# swimate_display.net
KiCad netlist of a schematic drawn in EAGLE
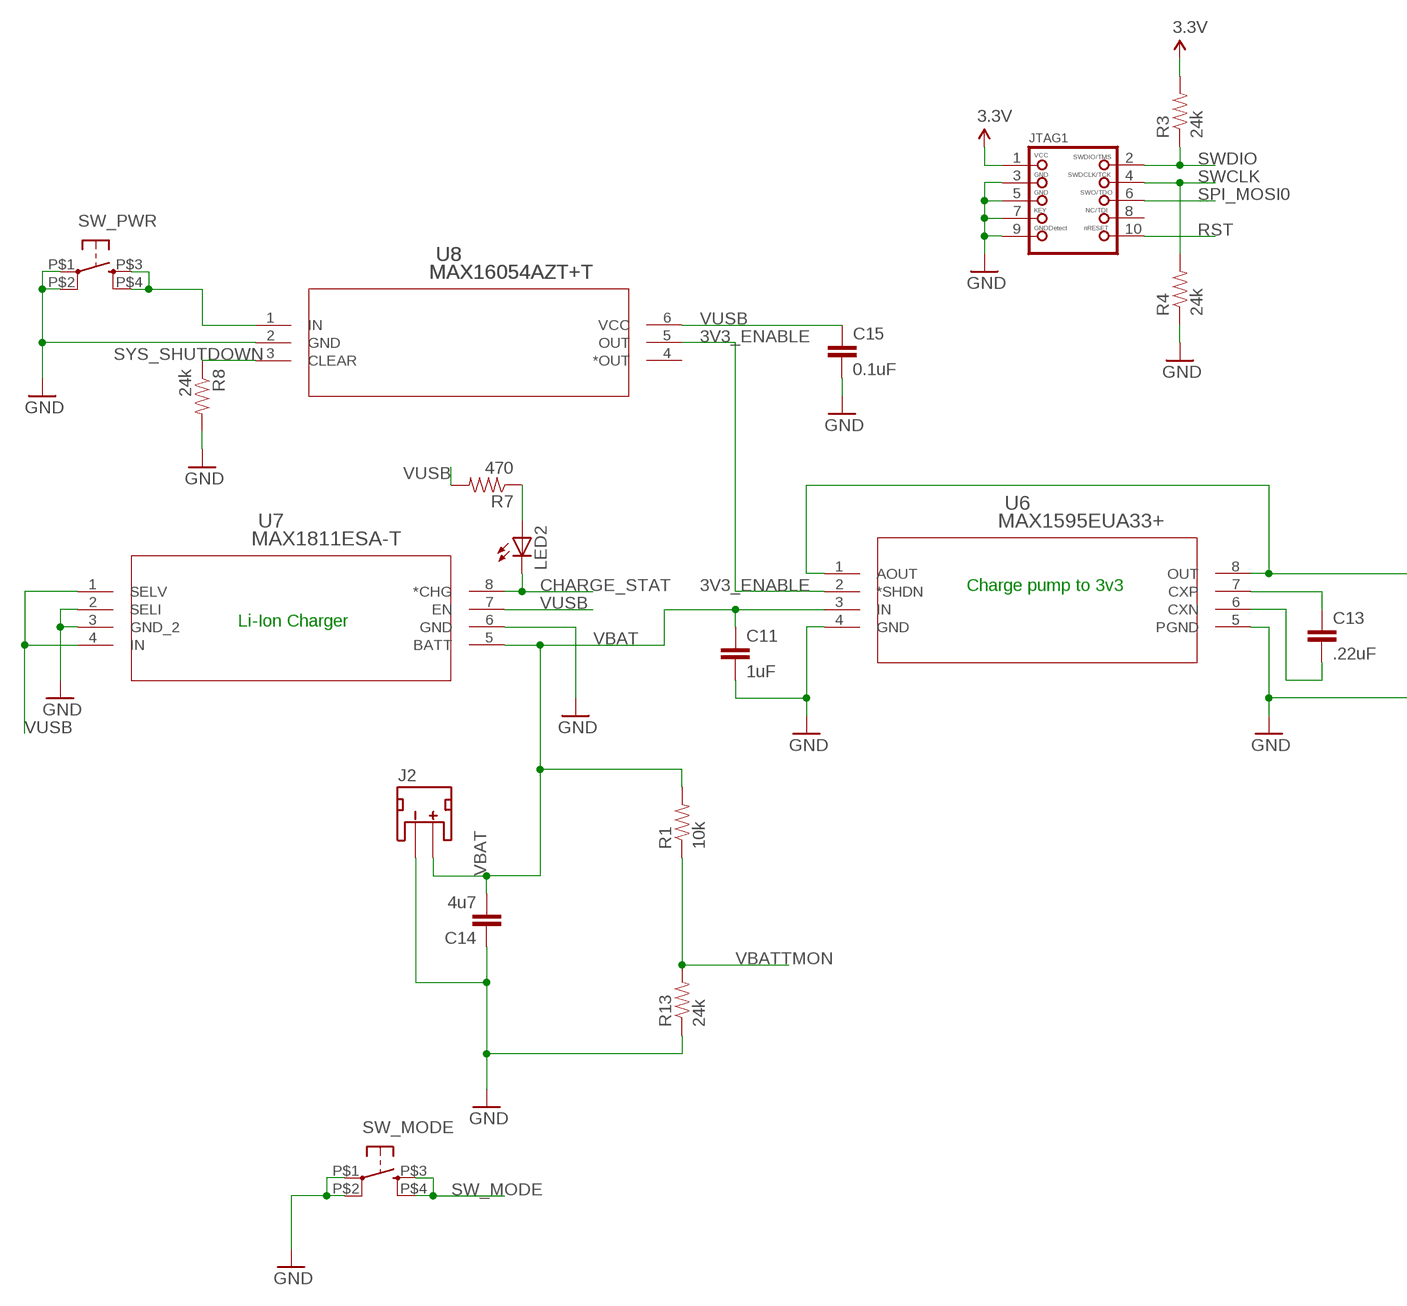
[diagram p0: schematic, sheet 1, part 1 of 2]
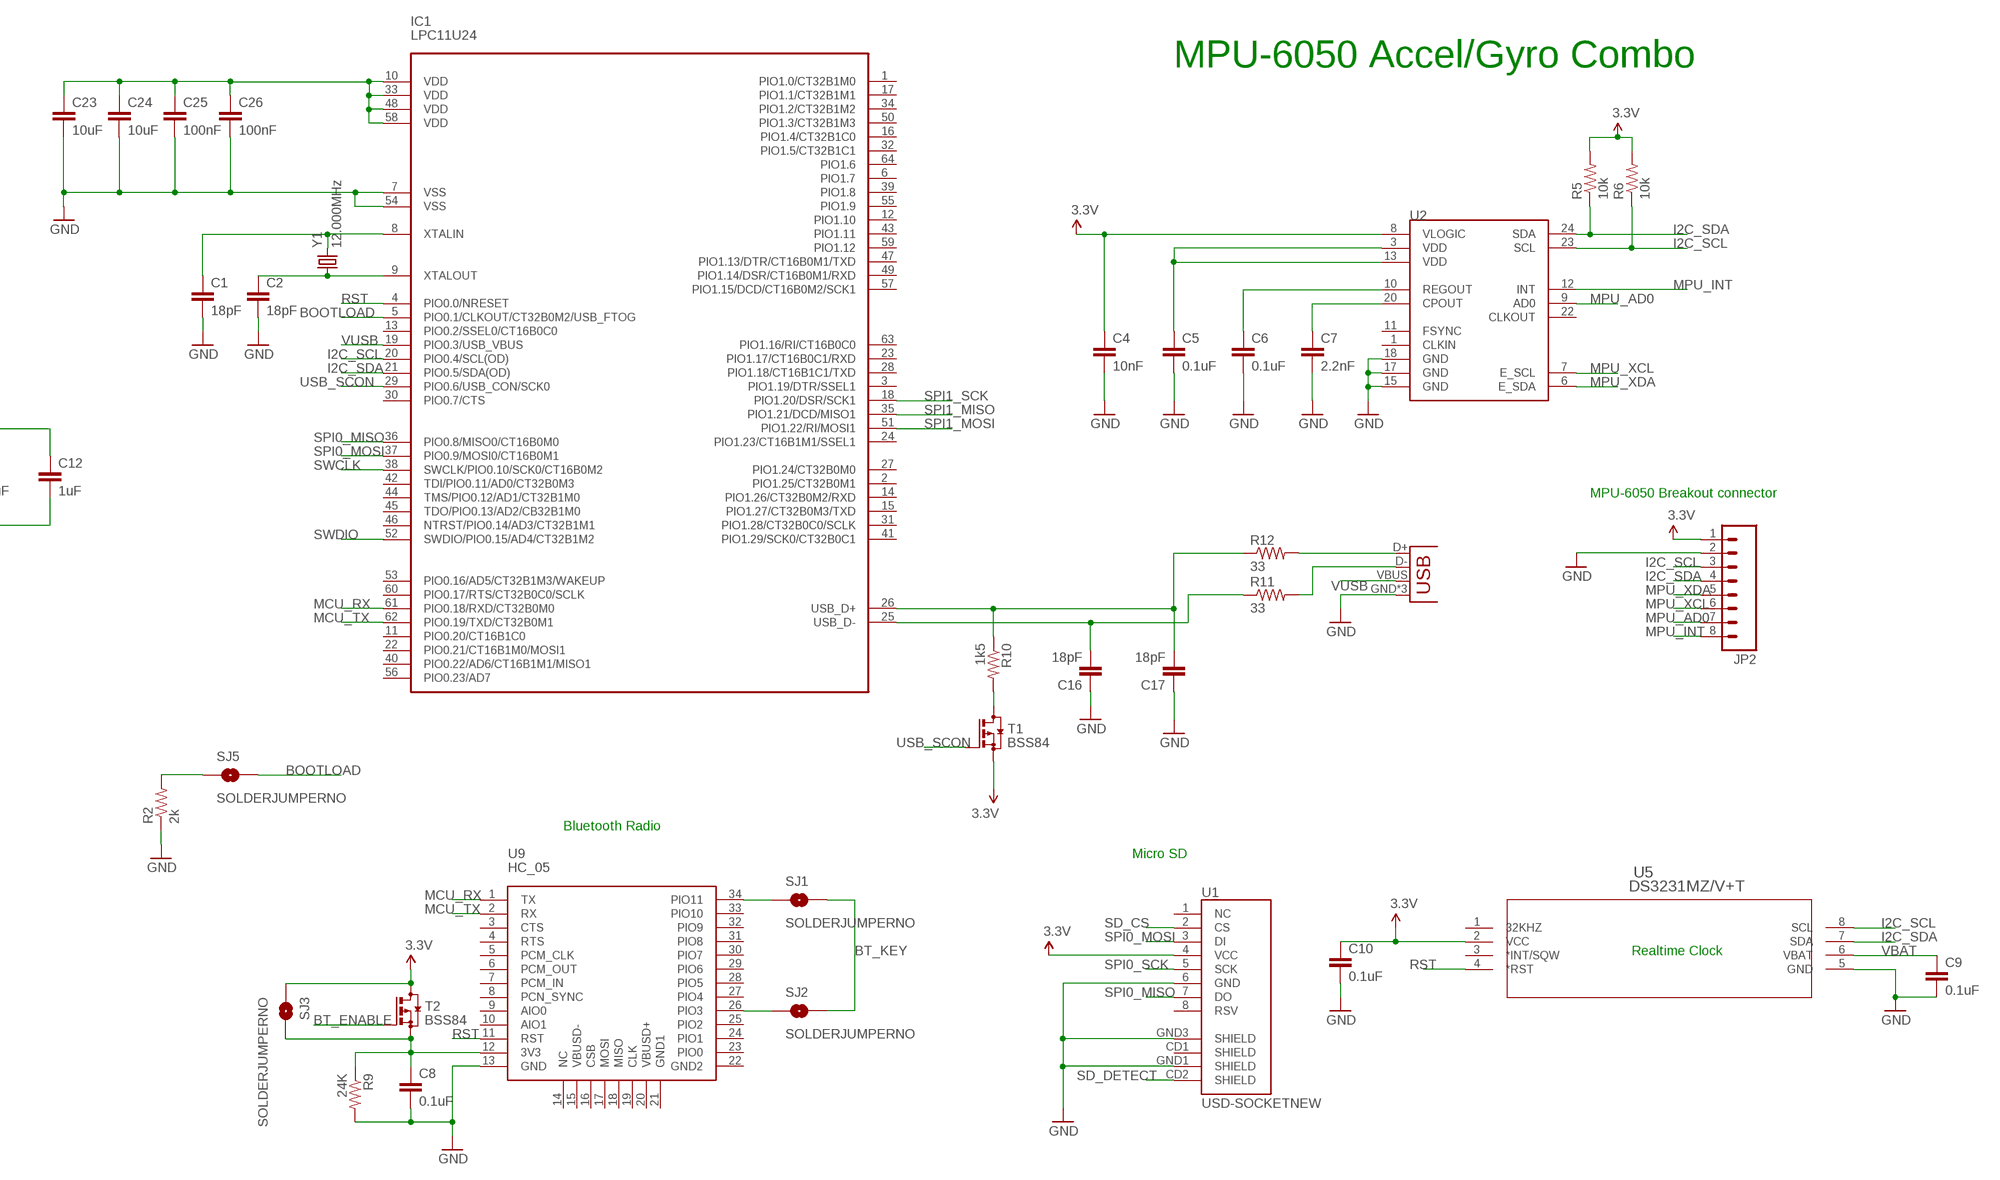
[diagram p1: schematic, sheet 1, part 2 of 2]

(export (version "E")
  (design (tool "Eeschema 10.0.6"))
  (components
    (comp (ref "C1")
      (value "18pF")
      (footprint "eagle-import:0805")
      (libsource (lib "eagle-import") (part "SparkFun-Passives_CAP0805"))
    )
    (comp (ref "C2")
      (value "18pF")
      (footprint "eagle-import:0805")
      (libsource (lib "eagle-import") (part "SparkFun-Passives_CAP0805"))
    )
    (comp (ref "C4")
      (value "10nF")
      (footprint "eagle-import:0805")
      (libsource (lib "eagle-import") (part "SparkFun-Passives_CAP0805"))
    )
    (comp (ref "C5")
      (value "0.1uF")
      (footprint "eagle-import:0805")
      (libsource (lib "eagle-import") (part "SparkFun-Passives_CAP0805"))
    )
    (comp (ref "C6")
      (value "0.1uF")
      (footprint "eagle-import:0805")
      (libsource (lib "eagle-import") (part "SparkFun-Passives_CAP0805"))
    )
    (comp (ref "C7")
      (value "2.2nF")
      (footprint "eagle-import:0805")
      (libsource (lib "eagle-import") (part "SparkFun-Passives_CAP0805"))
    )
    (comp (ref "C8")
      (value "0.1uF")
      (footprint "eagle-import:0805")
      (libsource (lib "eagle-import") (part "SparkFun-Passives_CAP0805"))
    )
    (comp (ref "C9")
      (value "0.1uF")
      (footprint "eagle-import:0805")
      (libsource (lib "eagle-import") (part "SparkFun-Passives_CAP0805"))
    )
    (comp (ref "C10")
      (value "0.1uF")
      (footprint "eagle-import:0805")
      (libsource (lib "eagle-import") (part "SparkFun-Passives_CAP0805"))
    )
    (comp (ref "C11")
      (value "1uF")
      (footprint "eagle-import:1206")
      (libsource (lib "eagle-import") (part "CAP1206"))
    )
    (comp (ref "C12")
      (value "1uF")
      (footprint "eagle-import:1206")
      (libsource (lib "eagle-import") (part "CAP1206"))
    )
    (comp (ref "C13")
      (value ".22uF")
      (footprint "eagle-import:0805")
      (libsource (lib "eagle-import") (part "SparkFun-Passives_CAP0805"))
    )
    (comp (ref "C14")
      (value "4u7")
      (footprint "eagle-import:1206")
      (libsource (lib "eagle-import") (part "SparkFun-Passives_CAP1206"))
    )
    (comp (ref "C15")
      (value "0.1uF")
      (footprint "eagle-import:0805")
      (libsource (lib "eagle-import") (part "SparkFun-Passives_CAP0805"))
    )
    (comp (ref "C16")
      (value "18pF")
      (footprint "eagle-import:0805")
      (libsource (lib "eagle-import") (part "SparkFun-Passives_CAP0805"))
    )
    (comp (ref "C17")
      (value "18pF")
      (footprint "eagle-import:0805")
      (libsource (lib "eagle-import") (part "SparkFun-Passives_CAP0805"))
    )
    (comp (ref "C23")
      (value "10uF")
      (footprint "eagle-import:0805")
      (libsource (lib "eagle-import") (part "CAP0805"))
    )
    (comp (ref "C24")
      (value "10uF")
      (footprint "eagle-import:0805")
      (libsource (lib "eagle-import") (part "CAP0805"))
    )
    (comp (ref "C25")
      (value "100nF")
      (footprint "eagle-import:0805")
      (libsource (lib "eagle-import") (part "CAP0805"))
    )
    (comp (ref "C26")
      (value "100nF")
      (footprint "eagle-import:0805")
      (libsource (lib "eagle-import") (part "CAP0805"))
    )
    (comp (ref "IC1")
      (value "LPC11U24")
      (footprint "eagle-import:MBED-ICS_LQFP64")
      (libsource (lib "eagle-import") (part "LPC11U24"))
    )
    (comp (ref "J2")
      (value "JST_2MM_MALE")
      (footprint "eagle-import:JST-2-SMD")
      (libsource (lib "eagle-import") (part "JST_2MM_MALE"))
    )
    (comp (ref "JP2")
      (value "M08")
      (footprint "eagle-import:1X08_PIN1_NO_SILK")
      (libsource (lib "eagle-import") (part "M08"))
    )
    (comp (ref "JP3")
      (value "USB-MICROB")
      (footprint "eagle-import:USB-MICROB")
      (libsource (lib "eagle-import") (part "USB-MICROB"))
    )
    (comp (ref "JTAG1")
      (value "JTAG-CORTEXM3")
      (footprint "eagle-import:2X05_1.27MM_SMT")
      (libsource (lib "eagle-import") (part "JTAG-CORTEXM3"))
    )
    (comp (ref "LED2")
      (value "LED1206")
      (footprint "eagle-import:LED-1206")
      (libsource (lib "eagle-import") (part "LED1206"))
    )
    (comp (ref "R1")
      (value "10k")
      (footprint "eagle-import:0603-RES")
      (libsource (lib "eagle-import") (part "RESISTOR0603-RES"))
    )
    (comp (ref "R2")
      (value "2k")
      (footprint "eagle-import:0805")
      (libsource (lib "eagle-import") (part "RESISTOR0805-RES"))
    )
    (comp (ref "R3")
      (value "24k")
      (footprint "eagle-import:0805")
      (libsource (lib "eagle-import") (part "RESISTOR0805-RES"))
    )
    (comp (ref "R4")
      (value "24k")
      (footprint "eagle-import:0805")
      (libsource (lib "eagle-import") (part "RESISTOR0805-RES"))
    )
    (comp (ref "R5")
      (value "10k")
      (footprint "eagle-import:0805")
      (libsource (lib "eagle-import") (part "RESISTOR0805-RES"))
    )
    (comp (ref "R6")
      (value "10k")
      (footprint "eagle-import:0805")
      (libsource (lib "eagle-import") (part "RESISTOR0805-RES"))
    )
    (comp (ref "R7")
      (value "470")
      (footprint "eagle-import:0805")
      (libsource (lib "eagle-import") (part "RESISTOR0805-RES"))
    )
    (comp (ref "R8")
      (value "24k")
      (footprint "eagle-import:0805")
      (libsource (lib "eagle-import") (part "RESISTOR0805-RES"))
    )
    (comp (ref "R9")
      (value "24K")
      (footprint "eagle-import:0805")
      (libsource (lib "eagle-import") (part "RESISTOR0805-RES"))
    )
    (comp (ref "R10")
      (value "1k5")
      (footprint "eagle-import:0805")
      (libsource (lib "eagle-import") (part "RESISTOR0805-RES"))
    )
    (comp (ref "R11")
      (value "33")
      (footprint "eagle-import:0805")
      (libsource (lib "eagle-import") (part "RESISTOR0805-RES"))
    )
    (comp (ref "R12")
      (value "33")
      (footprint "eagle-import:0805")
      (libsource (lib "eagle-import") (part "RESISTOR0805-RES"))
    )
    (comp (ref "R13")
      (value "24k")
      (footprint "eagle-import:0603-RES")
      (libsource (lib "eagle-import") (part "RESISTOR0603-RES"))
    )
    (comp (ref "SJ1")
      (value "SOLDERJUMPERNO")
      (footprint "eagle-import:SJ_2S-NO")
      (libsource (lib "eagle-import") (part "SOLDERJUMPERNO"))
    )
    (comp (ref "SJ2")
      (value "SOLDERJUMPERNO")
      (footprint "eagle-import:SJ_2S-NO")
      (libsource (lib "eagle-import") (part "SOLDERJUMPERNO"))
    )
    (comp (ref "SJ3")
      (value "SOLDERJUMPERNO")
      (footprint "eagle-import:SJ_2S-NO")
      (libsource (lib "eagle-import") (part "SOLDERJUMPERNO"))
    )
    (comp (ref "SJ5")
      (value "SOLDERJUMPERNO")
      (footprint "eagle-import:SJ_2S-NO")
      (libsource (lib "eagle-import") (part "SOLDERJUMPERNO"))
    )
    (comp (ref "SW_MODE")
      (value "TAC_SWITCHKSA_SEALED")
      (footprint "eagle-import:KSA_SEALED_TAC_SWITCH")
      (libsource (lib "eagle-import") (part "TAC_SWITCHKSA_SEALED"))
    )
    (comp (ref "SW_PWR")
      (value "TAC_SWITCHKSA_SEALED")
      (footprint "eagle-import:KSA_SEALED_TAC_SWITCH")
      (libsource (lib "eagle-import") (part "TAC_SWITCHKSA_SEALED"))
    )
    (comp (ref "T1")
      (value "BSS84")
      (footprint "eagle-import:SOT23")
      (libsource (lib "eagle-import") (part "BSS84"))
    )
    (comp (ref "T2")
      (value "BSS84")
      (footprint "eagle-import:SOT23")
      (libsource (lib "eagle-import") (part "BSS84"))
    )
    (comp (ref "U1")
      (value "USD-SOCKETNEW")
      (footprint "eagle-import:MICRO-SD-SOCKET-PP")
      (libsource (lib "eagle-import") (part "USD-SOCKETNEW"))
    )
    (comp (ref "U2")
      (value "MPU-9150QFN-24-NP")
      (footprint "eagle-import:QFN-24-NP")
      (libsource (lib "eagle-import") (part "MPU-9150QFN-24-NP"))
    )
    (comp (ref "U5")
      (value "DS3231MZ/V+T")
      (footprint "eagle-import:21-0041B_8")
      (libsource (lib "eagle-import") (part "DS3231MZ/V+T"))
    )
    (comp (ref "U6")
      (value "MAX1595EUA33+")
      (footprint "eagle-import:21-0036K")
      (libsource (lib "eagle-import") (part "MAX1595EUA33+"))
    )
    (comp (ref "U7")
      (value "MAX1811ESA-T")
      (footprint "eagle-import:21-0041B_8")
      (libsource (lib "eagle-import") (part "MAX1811ESA-T"))
    )
    (comp (ref "U8")
      (value "MAX16054AZT+T")
      (footprint "eagle-import:21-0114C")
      (libsource (lib "eagle-import") (part "MAX16054AZT+T"))
    )
    (comp (ref "U9")
      (value "HC_05")
      (footprint "eagle-import:BLUETOOTH_SMD")
      (libsource (lib "eagle-import") (part "HC_05"))
    )
    (comp (ref "Y1")
      (value "12.000MHz")
      (footprint "eagle-import:CRYSTAL-SMD-10.5X4.8-2PIN")
      (libsource (lib "eagle-import") (part "CRYSTAL10.5X4.8"))
    )
  )
  (nets
    (net (code "1") (name "/3V3_ENABLE") (class "Default")
      (node (ref "U6") (pin "2") (pinfunction "*SHDN_2") (pintype "passive"))
      (node (ref "U8") (pin "5") (pinfunction "OUT_5") (pintype "output"))
    )
    (net (code "2") (name "/BOOTLOAD") (class "Default")
      (node (ref "IC1") (pin "5") (pinfunction "PIO0.1/CLKOUT/CT32B0M2/USB_FTOG_5") (pintype "bidirectional"))
      (node (ref "SJ5") (pin "2") (pinfunction "2_2") (pintype "passive"))
    )
    (net (code "3") (name "/BT_ENABLE") (class "Default")
      (node (ref "T2") (pin "1") (pinfunction "G_1") (pintype "passive"))
    )
    (net (code "4") (name "/BT_KEY") (class "Default")
      (node (ref "SJ1") (pin "2") (pinfunction "2_2") (pintype "passive"))
      (node (ref "SJ2") (pin "2") (pinfunction "2_2") (pintype "passive"))
    )
    (net (code "5") (name "/CHARGE_STAT") (class "Default")
      (node (ref "LED2") (pin "C") (pinfunction "C_C") (pintype "passive"))
      (node (ref "U7") (pin "8") (pinfunction "*CHG_8") (pintype "bidirectional"))
    )
    (net (code "6") (name "/I2C_SCL") (class "Default")
      (node (ref "IC1") (pin "20") (pinfunction "PIO0.4/SCL(OD)_20") (pintype "bidirectional"))
      (node (ref "JP2") (pin "3") (pinfunction "3_3") (pintype "passive"))
      (node (ref "R6") (pin "1") (pinfunction "1_1") (pintype "passive"))
      (node (ref "U2") (pin "23") (pinfunction "SCL_23") (pintype "bidirectional"))
      (node (ref "U5") (pin "8") (pinfunction "SCL_8") (pintype "passive"))
    )
    (net (code "7") (name "/I2C_SDA") (class "Default")
      (node (ref "IC1") (pin "21") (pinfunction "PIO0.5/SDA(OD)_21") (pintype "bidirectional"))
      (node (ref "JP2") (pin "4") (pinfunction "4_4") (pintype "passive"))
      (node (ref "R5") (pin "1") (pinfunction "1_1") (pintype "passive"))
      (node (ref "U2") (pin "24") (pinfunction "SDA_24") (pintype "bidirectional"))
      (node (ref "U5") (pin "7") (pinfunction "SDA_7") (pintype "passive"))
    )
    (net (code "8") (name "/MCU_RX") (class "Default")
      (node (ref "IC1") (pin "61") (pinfunction "PIO0.18/RXD/CT32B0M0_61") (pintype "bidirectional"))
      (node (ref "U9") (pin "1") (pinfunction "TX_1") (pintype "bidirectional"))
    )
    (net (code "9") (name "/MCU_TX") (class "Default")
      (node (ref "IC1") (pin "62") (pinfunction "PIO0.19/TXD/CT32B0M1_62") (pintype "bidirectional"))
      (node (ref "U9") (pin "2") (pinfunction "RX_2") (pintype "bidirectional"))
    )
    (net (code "10") (name "/MPU_AD0") (class "Default")
      (node (ref "JP2") (pin "7") (pinfunction "7_7") (pintype "passive"))
      (node (ref "U2") (pin "9") (pinfunction "AD0_9") (pintype "bidirectional"))
    )
    (net (code "11") (name "/MPU_INT") (class "Default")
      (node (ref "JP2") (pin "8") (pinfunction "8_8") (pintype "passive"))
      (node (ref "U2") (pin "12") (pinfunction "INT_12") (pintype "bidirectional"))
    )
    (net (code "12") (name "/MPU_XCL") (class "Default")
      (node (ref "JP2") (pin "6") (pinfunction "6_6") (pintype "passive"))
      (node (ref "U2") (pin "7") (pinfunction "E_SCL_7") (pintype "bidirectional"))
    )
    (net (code "13") (name "/MPU_XDA") (class "Default")
      (node (ref "JP2") (pin "5") (pinfunction "5_5") (pintype "passive"))
      (node (ref "U2") (pin "6") (pinfunction "E_SDA_6") (pintype "bidirectional"))
    )
    (net (code "14") (name "/RST") (class "Default")
      (node (ref "IC1") (pin "4") (pinfunction "PIO0.0/NRESET_4") (pintype "bidirectional"))
      (node (ref "JTAG1") (pin "10") (pinfunction "10_10") (pintype "passive"))
      (node (ref "U5") (pin "4") (pinfunction "*RST_4") (pintype "passive"))
      (node (ref "U9") (pin "11") (pinfunction "RST_11") (pintype "bidirectional"))
    )
    (net (code "15") (name "/SD_CS") (class "Default")
      (node (ref "U1") (pin "2") (pinfunction "CS_2") (pintype "bidirectional"))
    )
    (net (code "16") (name "/SD_DETECT") (class "Default")
      (node (ref "U1") (pin "CD2") (pinfunction "SHIELD_CD2") (pintype "bidirectional"))
    )
    (net (code "17") (name "/SPI0_MISO") (class "Default")
      (node (ref "IC1") (pin "36") (pinfunction "PIO0.8/MISO0/CT16B0M0_36") (pintype "bidirectional"))
      (node (ref "U1") (pin "7") (pinfunction "DO_7") (pintype "bidirectional"))
    )
    (net (code "18") (name "/SPI0_MOSI") (class "Default")
      (node (ref "IC1") (pin "37") (pinfunction "PIO0.9/MOSI0/CT16B0M1_37") (pintype "bidirectional"))
      (node (ref "U1") (pin "3") (pinfunction "DI_3") (pintype "bidirectional"))
    )
    (net (code "19") (name "/SPI0_SCK") (class "Default")
      (node (ref "U1") (pin "5") (pinfunction "SCK_5") (pintype "bidirectional"))
    )
    (net (code "20") (name "/SPI1_MISO") (class "Default")
      (node (ref "IC1") (pin "35") (pinfunction "PIO1.21/DCD/MISO1_35") (pintype "bidirectional"))
    )
    (net (code "21") (name "/SPI1_MOSI") (class "Default")
      (node (ref "IC1") (pin "51") (pinfunction "PIO1.22/RI/MOSI1_51") (pintype "bidirectional"))
    )
    (net (code "22") (name "/SPI1_SCK") (class "Default")
      (node (ref "IC1") (pin "18") (pinfunction "PIO1.20/DSR/SCK1_18") (pintype "bidirectional"))
    )
    (net (code "23") (name "/SPI_MOSI0") (class "Default")
      (node (ref "JTAG1") (pin "6") (pinfunction "6_6") (pintype "passive"))
    )
    (net (code "24") (name "/SWCLK") (class "Default")
      (node (ref "IC1") (pin "38") (pinfunction "SWCLK/PIO0.10/SCK0/CT16B0M2_38") (pintype "bidirectional"))
      (node (ref "JTAG1") (pin "4") (pinfunction "4_4") (pintype "passive"))
      (node (ref "R4") (pin "2") (pinfunction "2_2") (pintype "passive"))
    )
    (net (code "25") (name "/SWDIO") (class "Default")
      (node (ref "IC1") (pin "52") (pinfunction "SWDIO/PIO0.15/AD4/CT32B1M2_52") (pintype "bidirectional"))
      (node (ref "JTAG1") (pin "2") (pinfunction "2_2") (pintype "passive"))
      (node (ref "R3") (pin "1") (pinfunction "1_1") (pintype "passive"))
    )
    (net (code "26") (name "/SW_MODE") (class "Default")
      (node (ref "SW_MODE") (pin "P$3") (pinfunction "3_P$3") (pintype "passive"))
      (node (ref "SW_MODE") (pin "P$4") (pinfunction "4_P$4") (pintype "passive"))
    )
    (net (code "27") (name "/SYS_SHUTDOWN") (class "Default")
      (node (ref "R8") (pin "1") (pinfunction "1_1") (pintype "passive"))
      (node (ref "U8") (pin "3") (pinfunction "CLEAR_3") (pintype "bidirectional"))
    )
    (net (code "28") (name "/USB_SCON") (class "Default")
      (node (ref "IC1") (pin "29") (pinfunction "PIO0.6/USB_CON/SCK0_29") (pintype "bidirectional"))
      (node (ref "T1") (pin "1") (pinfunction "G_1") (pintype "passive"))
    )
    (net (code "29") (name "/VBAT") (class "Default")
      (node (ref "C11") (pin "1") (pinfunction "1_1") (pintype "passive"))
      (node (ref "C14") (pin "2") (pinfunction "2_2") (pintype "passive"))
      (node (ref "C9") (pin "1") (pinfunction "1_1") (pintype "passive"))
      (node (ref "J2") (pin "2") (pinfunction "+_2") (pintype "bidirectional"))
      (node (ref "R1") (pin "2") (pinfunction "2_2") (pintype "passive"))
      (node (ref "U5") (pin "6") (pinfunction "VBAT_6") (pintype "power_in"))
      (node (ref "U6") (pin "3") (pinfunction "IN_3") (pintype "input"))
      (node (ref "U7") (pin "5") (pinfunction "BATT_5") (pintype "bidirectional"))
    )
    (net (code "30") (name "/VBATTMON") (class "Default")
      (node (ref "R1") (pin "1") (pinfunction "1_1") (pintype "passive"))
      (node (ref "R13") (pin "2") (pinfunction "2_2") (pintype "passive"))
    )
    (net (code "31") (name "/VUSB") (class "Default")
      (node (ref "C15") (pin "1") (pinfunction "1_1") (pintype "passive"))
      (node (ref "IC1") (pin "19") (pinfunction "PIO0.3/USB_VBUS_19") (pintype "bidirectional"))
      (node (ref "JP3") (pin "VBUS") (pinfunction "VBUS_VBUS") (pintype "bidirectional"))
      (node (ref "R7") (pin "2") (pinfunction "2_2") (pintype "passive"))
      (node (ref "U7") (pin "1") (pinfunction "SELV_1") (pintype "bidirectional"))
      (node (ref "U7") (pin "4") (pinfunction "IN_4") (pintype "input"))
      (node (ref "U7") (pin "7") (pinfunction "EN_7") (pintype "bidirectional"))
      (node (ref "U8") (pin "6") (pinfunction "VCC_6") (pintype "power_in"))
    )
    (net (code "32") (name "3.3V") (class "Default")
      (node (ref "C10") (pin "1") (pinfunction "1_1") (pintype "passive"))
      (node (ref "C4") (pin "1") (pinfunction "1_1") (pintype "passive"))
      (node (ref "JP2") (pin "1") (pinfunction "1_1") (pintype "passive"))
      (node (ref "JTAG1") (pin "1") (pinfunction "1_1") (pintype "passive"))
      (node (ref "R3") (pin "2") (pinfunction "2_2") (pintype "passive"))
      (node (ref "R5") (pin "2") (pinfunction "2_2") (pintype "passive"))
      (node (ref "R6") (pin "2") (pinfunction "2_2") (pintype "passive"))
      (node (ref "SJ3") (pin "1") (pinfunction "1_1") (pintype "passive"))
      (node (ref "T1") (pin "2") (pinfunction "S_2") (pintype "passive"))
      (node (ref "T2") (pin "3") (pinfunction "D_3") (pintype "passive"))
      (node (ref "U1") (pin "4") (pinfunction "VCC_4") (pintype "bidirectional"))
      (node (ref "U2") (pin "8") (pinfunction "VLOGIC_8") (pintype "bidirectional"))
      (node (ref "U5") (pin "2") (pinfunction "VCC_2") (pintype "power_in"))
    )
    (net (code "33") (name "GND") (class "Default")
      (node (ref "C1") (pin "2") (pinfunction "2_2") (pintype "passive"))
      (node (ref "C10") (pin "2") (pinfunction "2_2") (pintype "passive"))
      (node (ref "C11") (pin "2") (pinfunction "2_2") (pintype "passive"))
      (node (ref "C12") (pin "2") (pinfunction "2_2") (pintype "passive"))
      (node (ref "C14") (pin "1") (pinfunction "1_1") (pintype "passive"))
      (node (ref "C15") (pin "2") (pinfunction "2_2") (pintype "passive"))
      (node (ref "C16") (pin "1") (pinfunction "1_1") (pintype "passive"))
      (node (ref "C17") (pin "1") (pinfunction "1_1") (pintype "passive"))
      (node (ref "C2") (pin "2") (pinfunction "2_2") (pintype "passive"))
      (node (ref "C23") (pin "2") (pinfunction "2_2") (pintype "passive"))
      (node (ref "C24") (pin "2") (pinfunction "2_2") (pintype "passive"))
      (node (ref "C25") (pin "2") (pinfunction "2_2") (pintype "passive"))
      (node (ref "C26") (pin "2") (pinfunction "2_2") (pintype "passive"))
      (node (ref "C4") (pin "2") (pinfunction "2_2") (pintype "passive"))
      (node (ref "C5") (pin "2") (pinfunction "2_2") (pintype "passive"))
      (node (ref "C6") (pin "2") (pinfunction "2_2") (pintype "passive"))
      (node (ref "C7") (pin "2") (pinfunction "2_2") (pintype "passive"))
      (node (ref "C8") (pin "2") (pinfunction "2_2") (pintype "passive"))
      (node (ref "C9") (pin "2") (pinfunction "2_2") (pintype "passive"))
      (node (ref "IC1") (pin "54") (pinfunction "VSS_54") (pintype "bidirectional"))
      (node (ref "IC1") (pin "7") (pinfunction "VSS_7") (pintype "bidirectional"))
      (node (ref "J2") (pin "1") (pinfunction "-_1") (pintype "bidirectional"))
      (node (ref "JP2") (pin "2") (pinfunction "2_2") (pintype "passive"))
      (node (ref "JP3") (pin "GND") (pinfunction "GND_GND") (pintype "bidirectional"))
      (node (ref "JP3") (pin "MT1") (pinfunction "GND_MT1") (pintype "bidirectional"))
      (node (ref "JP3") (pin "MT2") (pinfunction "GND_MT2") (pintype "bidirectional"))
      (node (ref "JTAG1") (pin "3") (pinfunction "3_3") (pintype "passive"))
      (node (ref "JTAG1") (pin "5") (pinfunction "5_5") (pintype "passive"))
      (node (ref "JTAG1") (pin "7") (pinfunction "7_7") (pintype "passive"))
      (node (ref "JTAG1") (pin "9") (pinfunction "9_9") (pintype "passive"))
      (node (ref "R13") (pin "1") (pinfunction "1_1") (pintype "passive"))
      (node (ref "R2") (pin "1") (pinfunction "1_1") (pintype "passive"))
      (node (ref "R4") (pin "1") (pinfunction "1_1") (pintype "passive"))
      (node (ref "R8") (pin "2") (pinfunction "2_2") (pintype "passive"))
      (node (ref "R9") (pin "2") (pinfunction "2_2") (pintype "passive"))
      (node (ref "SW_MODE") (pin "P$1") (pinfunction "1_P$1") (pintype "passive"))
      (node (ref "SW_MODE") (pin "P$2") (pinfunction "2_P$2") (pintype "passive"))
      (node (ref "SW_PWR") (pin "P$1") (pinfunction "1_P$1") (pintype "passive"))
      (node (ref "SW_PWR") (pin "P$2") (pinfunction "2_P$2") (pintype "passive"))
      (node (ref "U1") (pin "6") (pinfunction "GND_6") (pintype "bidirectional"))
      (node (ref "U1") (pin "GND1") (pinfunction "SHIELD_GND1") (pintype "bidirectional"))
      (node (ref "U1") (pin "GND3") (pinfunction "SHIELD_GND3") (pintype "bidirectional"))
      (node (ref "U2") (pin "15") (pinfunction "GND_15") (pintype "bidirectional"))
      (node (ref "U2") (pin "17") (pinfunction "GND_17") (pintype "bidirectional"))
      (node (ref "U2") (pin "18") (pinfunction "GND_18") (pintype "bidirectional"))
      (node (ref "U5") (pin "5") (pinfunction "GND_5") (pintype "power_in"))
      (node (ref "U6") (pin "4") (pinfunction "GND_4") (pintype "power_in"))
      (node (ref "U6") (pin "5") (pinfunction "PGND_5") (pintype "power_in"))
      (node (ref "U7") (pin "2") (pinfunction "SELI_2") (pintype "bidirectional"))
      (node (ref "U7") (pin "3") (pinfunction "GND_2_3") (pintype "power_in"))
      (node (ref "U7") (pin "6") (pinfunction "GND_6") (pintype "power_in"))
      (node (ref "U8") (pin "2") (pinfunction "GND_2") (pintype "power_in"))
      (node (ref "U9") (pin "13") (pinfunction "GND_13") (pintype "bidirectional"))
    )
    (net (code "34") (name "Net-(C5-Pad1)") (class "Default")
      (node (ref "C5") (pin "1") (pinfunction "1_1") (pintype "passive"))
      (node (ref "U2") (pin "13") (pinfunction "VDD_13") (pintype "bidirectional"))
      (node (ref "U2") (pin "3") (pinfunction "VDD_3") (pintype "bidirectional"))
    )
    (net (code "35") (name "Net-(C23-Pad1)") (class "Default")
      (node (ref "C23") (pin "1") (pinfunction "1_1") (pintype "passive"))
      (node (ref "C24") (pin "1") (pinfunction "1_1") (pintype "passive"))
      (node (ref "C25") (pin "1") (pinfunction "1_1") (pintype "passive"))
      (node (ref "C26") (pin "1") (pinfunction "1_1") (pintype "passive"))
      (node (ref "IC1") (pin "10") (pinfunction "VDD_10") (pintype "bidirectional"))
      (node (ref "IC1") (pin "33") (pinfunction "VDD_33") (pintype "bidirectional"))
      (node (ref "IC1") (pin "48") (pinfunction "VDD_48") (pintype "bidirectional"))
      (node (ref "IC1") (pin "58") (pinfunction "VDD_58") (pintype "bidirectional"))
    )
    (net (code "36") (name "Net-(IC1-USB_D+)") (class "Default")
      (node (ref "C17") (pin "2") (pinfunction "2_2") (pintype "passive"))
      (node (ref "IC1") (pin "26") (pinfunction "USB_D+_26") (pintype "bidirectional"))
      (node (ref "R10") (pin "1") (pinfunction "1_1") (pintype "passive"))
      (node (ref "R12") (pin "1") (pinfunction "1_1") (pintype "passive"))
    )
    (net (code "37") (name "Net-(IC1-USB_D-)") (class "Default")
      (node (ref "C16") (pin "2") (pinfunction "2_2") (pintype "passive"))
      (node (ref "IC1") (pin "25") (pinfunction "USB_D-_25") (pintype "bidirectional"))
      (node (ref "R11") (pin "1") (pinfunction "1_1") (pintype "passive"))
    )
    (net (code "38") (name "Net-(IC1-XTALIN)") (class "Default")
      (node (ref "C1") (pin "1") (pinfunction "1_1") (pintype "passive"))
      (node (ref "IC1") (pin "8") (pinfunction "XTALIN_8") (pintype "bidirectional"))
      (node (ref "Y1") (pin "P$2") (pinfunction "2_P$2") (pintype "passive"))
    )
    (net (code "39") (name "Net-(IC1-XTALOUT)") (class "Default")
      (node (ref "C2") (pin "1") (pinfunction "1_1") (pintype "passive"))
      (node (ref "IC1") (pin "9") (pinfunction "XTALOUT_9") (pintype "bidirectional"))
      (node (ref "Y1") (pin "P$1") (pinfunction "1_P$1") (pintype "passive"))
    )
    (net (code "40") (name "Net-(JP3-PadD+)") (class "Default")
      (node (ref "JP3") (pin "D+") (pinfunction "D+_D+") (pintype "bidirectional"))
      (node (ref "R12") (pin "2") (pinfunction "2_2") (pintype "passive"))
    )
    (net (code "41") (name "Net-(JP3-PadD-)") (class "Default")
      (node (ref "JP3") (pin "D-") (pinfunction "D-_D-") (pintype "bidirectional"))
      (node (ref "R11") (pin "2") (pinfunction "2_2") (pintype "passive"))
    )
    (net (code "42") (name "Net-(LED2-PadA)") (class "Default")
      (node (ref "LED2") (pin "A") (pinfunction "A_A") (pintype "passive"))
      (node (ref "R7") (pin "1") (pinfunction "1_1") (pintype "passive"))
    )
    (net (code "43") (name "Net-(R2-Pad2)") (class "Default")
      (node (ref "R2") (pin "2") (pinfunction "2_2") (pintype "passive"))
      (node (ref "SJ5") (pin "1") (pinfunction "1_1") (pintype "passive"))
    )
    (net (code "44") (name "Net-(SW_PWR-3)") (class "Default")
      (node (ref "SW_PWR") (pin "P$3") (pinfunction "3_P$3") (pintype "passive"))
      (node (ref "SW_PWR") (pin "P$4") (pinfunction "4_P$4") (pintype "passive"))
      (node (ref "U8") (pin "1") (pinfunction "IN_1") (pintype "input"))
    )
    (net (code "45") (name "Net-(T1-D)") (class "Default")
      (node (ref "R10") (pin "2") (pinfunction "2_2") (pintype "passive"))
      (node (ref "T1") (pin "3") (pinfunction "D_3") (pintype "passive"))
    )
    (net (code "46") (name "Net-(T2-S)") (class "Default")
      (node (ref "C8") (pin "1") (pinfunction "1_1") (pintype "passive"))
      (node (ref "R9") (pin "1") (pinfunction "1_1") (pintype "passive"))
      (node (ref "SJ3") (pin "2") (pinfunction "2_2") (pintype "passive"))
      (node (ref "T2") (pin "2") (pinfunction "S_2") (pintype "passive"))
      (node (ref "U9") (pin "12") (pinfunction "3V3_12") (pintype "bidirectional"))
    )
    (net (code "47") (name "Net-(U2-CPOUT)") (class "Default")
      (node (ref "C7") (pin "1") (pinfunction "1_1") (pintype "passive"))
      (node (ref "U2") (pin "20") (pinfunction "CPOUT_20") (pintype "bidirectional"))
    )
    (net (code "48") (name "Net-(U2-REGOUT)") (class "Default")
      (node (ref "C6") (pin "1") (pinfunction "1_1") (pintype "passive"))
      (node (ref "U2") (pin "10") (pinfunction "REGOUT_10") (pintype "bidirectional"))
    )
    (net (code "49") (name "Net-(U6-AOUT)") (class "Default")
      (node (ref "C12") (pin "1") (pinfunction "1_1") (pintype "passive"))
      (node (ref "U6") (pin "1") (pinfunction "AOUT_1") (pintype "output"))
      (node (ref "U6") (pin "8") (pinfunction "OUT_8") (pintype "output"))
    )
    (net (code "50") (name "Net-(U6-CXN)") (class "Default")
      (node (ref "C13") (pin "2") (pinfunction "2_2") (pintype "passive"))
      (node (ref "U6") (pin "6") (pinfunction "CXN_6") (pintype "passive"))
    )
    (net (code "51") (name "Net-(U6-CXP)") (class "Default")
      (node (ref "C13") (pin "1") (pinfunction "1_1") (pintype "passive"))
      (node (ref "U6") (pin "7") (pinfunction "CXP_7") (pintype "passive"))
    )
    (net (code "52") (name "Net-(U9-PIO3)") (class "Default")
      (node (ref "SJ2") (pin "1") (pinfunction "1_1") (pintype "passive"))
      (node (ref "U9") (pin "26") (pinfunction "PIO3_26") (pintype "bidirectional"))
    )
    (net (code "53") (name "Net-(U9-PIO11)") (class "Default")
      (node (ref "SJ1") (pin "1") (pinfunction "1_1") (pintype "passive"))
      (node (ref "U9") (pin "34") (pinfunction "PIO11_34") (pintype "bidirectional"))
    )
    (net (code "54") (name "unconnected-(IC1-NTRST{slash}PIO0.14{slash}AD3{slash}CT32B1M1-Pad46)") (class "Default")
      (node (ref "IC1") (pin "46") (pinfunction "NTRST/PIO0.14/AD3/CT32B1M1_46") (pintype "bidirectional"))
    )
    (net (code "55") (name "unconnected-(IC1-PIO0.2{slash}SSEL0{slash}CT16B0C0-Pad13)") (class "Default")
      (node (ref "IC1") (pin "13") (pinfunction "PIO0.2/SSEL0/CT16B0C0_13") (pintype "bidirectional"))
    )
    (net (code "56") (name "unconnected-(IC1-PIO0.7{slash}CTS-Pad30)") (class "Default")
      (node (ref "IC1") (pin "30") (pinfunction "PIO0.7/CTS_30") (pintype "bidirectional"))
    )
    (net (code "57") (name "unconnected-(IC1-PIO0.16{slash}AD5{slash}CT32B1M3{slash}WAKEUP-Pad53)") (class "Default")
      (node (ref "IC1") (pin "53") (pinfunction "PIO0.16/AD5/CT32B1M3/WAKEUP_53") (pintype "bidirectional"))
    )
    (net (code "58") (name "unconnected-(IC1-PIO0.17{slash}RTS{slash}CT32B0C0{slash}SCLK-Pad60)") (class "Default")
      (node (ref "IC1") (pin "60") (pinfunction "PIO0.17/RTS/CT32B0C0/SCLK_60") (pintype "bidirectional"))
    )
    (net (code "59") (name "unconnected-(IC1-PIO0.20{slash}CT16B1C0-Pad11)") (class "Default")
      (node (ref "IC1") (pin "11") (pinfunction "PIO0.20/CT16B1C0_11") (pintype "bidirectional"))
    )
    (net (code "60") (name "unconnected-(IC1-PIO0.21{slash}CT16B1M0{slash}MOSI1-Pad22)") (class "Default")
      (node (ref "IC1") (pin "22") (pinfunction "PIO0.21/CT16B1M0/MOSI1_22") (pintype "bidirectional"))
    )
    (net (code "61") (name "unconnected-(IC1-PIO0.22{slash}AD6{slash}CT16B1M1{slash}MISO1-Pad40)") (class "Default")
      (node (ref "IC1") (pin "40") (pinfunction "PIO0.22/AD6/CT16B1M1/MISO1_40") (pintype "bidirectional"))
    )
    (net (code "62") (name "unconnected-(IC1-PIO0.23{slash}AD7-Pad56)") (class "Default")
      (node (ref "IC1") (pin "56") (pinfunction "PIO0.23/AD7_56") (pintype "bidirectional"))
    )
    (net (code "63") (name "unconnected-(IC1-PIO1.0{slash}CT32B1M0-Pad1)") (class "Default")
      (node (ref "IC1") (pin "1") (pinfunction "PIO1.0/CT32B1M0_1") (pintype "bidirectional"))
    )
    (net (code "64") (name "unconnected-(IC1-PIO1.1{slash}CT32B1M1-Pad17)") (class "Default")
      (node (ref "IC1") (pin "17") (pinfunction "PIO1.1/CT32B1M1_17") (pintype "bidirectional"))
    )
    (net (code "65") (name "unconnected-(IC1-PIO1.2{slash}CT32B1M2-Pad34)") (class "Default")
      (node (ref "IC1") (pin "34") (pinfunction "PIO1.2/CT32B1M2_34") (pintype "bidirectional"))
    )
    (net (code "66") (name "unconnected-(IC1-PIO1.3{slash}CT32B1M3-Pad50)") (class "Default")
      (node (ref "IC1") (pin "50") (pinfunction "PIO1.3/CT32B1M3_50") (pintype "bidirectional"))
    )
    (net (code "67") (name "unconnected-(IC1-PIO1.4{slash}CT32B1C0-Pad16)") (class "Default")
      (node (ref "IC1") (pin "16") (pinfunction "PIO1.4/CT32B1C0_16") (pintype "bidirectional"))
    )
    (net (code "68") (name "unconnected-(IC1-PIO1.5{slash}CT32B1C1-Pad32)") (class "Default")
      (node (ref "IC1") (pin "32") (pinfunction "PIO1.5/CT32B1C1_32") (pintype "bidirectional"))
    )
    (net (code "69") (name "unconnected-(IC1-PIO1.6-Pad64)") (class "Default")
      (node (ref "IC1") (pin "64") (pinfunction "PIO1.6_64") (pintype "bidirectional"))
    )
    (net (code "70") (name "unconnected-(IC1-PIO1.7-Pad6)") (class "Default")
      (node (ref "IC1") (pin "6") (pinfunction "PIO1.7_6") (pintype "bidirectional"))
    )
    (net (code "71") (name "unconnected-(IC1-PIO1.8-Pad39)") (class "Default")
      (node (ref "IC1") (pin "39") (pinfunction "PIO1.8_39") (pintype "bidirectional"))
    )
    (net (code "72") (name "unconnected-(IC1-PIO1.9-Pad55)") (class "Default")
      (node (ref "IC1") (pin "55") (pinfunction "PIO1.9_55") (pintype "bidirectional"))
    )
    (net (code "73") (name "unconnected-(IC1-PIO1.10-Pad12)") (class "Default")
      (node (ref "IC1") (pin "12") (pinfunction "PIO1.10_12") (pintype "bidirectional"))
    )
    (net (code "74") (name "unconnected-(IC1-PIO1.11-Pad43)") (class "Default")
      (node (ref "IC1") (pin "43") (pinfunction "PIO1.11_43") (pintype "bidirectional"))
    )
    (net (code "75") (name "unconnected-(IC1-PIO1.12-Pad59)") (class "Default")
      (node (ref "IC1") (pin "59") (pinfunction "PIO1.12_59") (pintype "bidirectional"))
    )
    (net (code "76") (name "unconnected-(IC1-PIO1.13{slash}DTR{slash}CT16B0M1{slash}TXD-Pad47)") (class "Default")
      (node (ref "IC1") (pin "47") (pinfunction "PIO1.13/DTR/CT16B0M1/TXD_47") (pintype "bidirectional"))
    )
    (net (code "77") (name "unconnected-(IC1-PIO1.14{slash}DSR{slash}CT16B0M1{slash}RXD-Pad49)") (class "Default")
      (node (ref "IC1") (pin "49") (pinfunction "PIO1.14/DSR/CT16B0M1/RXD_49") (pintype "bidirectional"))
    )
    (net (code "78") (name "unconnected-(IC1-PIO1.15{slash}DCD{slash}CT16B0M2{slash}SCK1-Pad57)") (class "Default")
      (node (ref "IC1") (pin "57") (pinfunction "PIO1.15/DCD/CT16B0M2/SCK1_57") (pintype "bidirectional"))
    )
    (net (code "79") (name "unconnected-(IC1-PIO1.16{slash}RI{slash}CT16B0C0-Pad63)") (class "Default")
      (node (ref "IC1") (pin "63") (pinfunction "PIO1.16/RI/CT16B0C0_63") (pintype "bidirectional"))
    )
    (net (code "80") (name "unconnected-(IC1-PIO1.17{slash}CT16B0C1{slash}RXD-Pad23)") (class "Default")
      (node (ref "IC1") (pin "23") (pinfunction "PIO1.17/CT16B0C1/RXD_23") (pintype "bidirectional"))
    )
    (net (code "81") (name "unconnected-(IC1-PIO1.18{slash}CT16B1C1{slash}TXD-Pad28)") (class "Default")
      (node (ref "IC1") (pin "28") (pinfunction "PIO1.18/CT16B1C1/TXD_28") (pintype "bidirectional"))
    )
    (net (code "82") (name "unconnected-(IC1-PIO1.19{slash}DTR{slash}SSEL1-Pad3)") (class "Default")
      (node (ref "IC1") (pin "3") (pinfunction "PIO1.19/DTR/SSEL1_3") (pintype "bidirectional"))
    )
    (net (code "83") (name "unconnected-(IC1-PIO1.23{slash}CT16B1M1{slash}SSEL1-Pad24)") (class "Default")
      (node (ref "IC1") (pin "24") (pinfunction "PIO1.23/CT16B1M1/SSEL1_24") (pintype "bidirectional"))
    )
    (net (code "84") (name "unconnected-(IC1-PIO1.24{slash}CT32B0M0-Pad27)") (class "Default")
      (node (ref "IC1") (pin "27") (pinfunction "PIO1.24/CT32B0M0_27") (pintype "bidirectional"))
    )
    (net (code "85") (name "unconnected-(IC1-PIO1.25{slash}CT32B0M1-Pad2)") (class "Default")
      (node (ref "IC1") (pin "2") (pinfunction "PIO1.25/CT32B0M1_2") (pintype "bidirectional"))
    )
    (net (code "86") (name "unconnected-(IC1-PIO1.26{slash}CT32B0M2{slash}RXD-Pad14)") (class "Default")
      (node (ref "IC1") (pin "14") (pinfunction "PIO1.26/CT32B0M2/RXD_14") (pintype "bidirectional"))
    )
    (net (code "87") (name "unconnected-(IC1-PIO1.27{slash}CT32B0M3{slash}TXD-Pad15)") (class "Default")
      (node (ref "IC1") (pin "15") (pinfunction "PIO1.27/CT32B0M3/TXD_15") (pintype "bidirectional"))
    )
    (net (code "88") (name "unconnected-(IC1-PIO1.28{slash}CT32B0C0{slash}SCLK-Pad31)") (class "Default")
      (node (ref "IC1") (pin "31") (pinfunction "PIO1.28/CT32B0C0/SCLK_31") (pintype "bidirectional"))
    )
    (net (code "89") (name "unconnected-(IC1-PIO1.29{slash}SCK0{slash}CT32B0C1-Pad41)") (class "Default")
      (node (ref "IC1") (pin "41") (pinfunction "PIO1.29/SCK0/CT32B0C1_41") (pintype "bidirectional"))
    )
    (net (code "90") (name "unconnected-(IC1-TDI{slash}PIO0.11{slash}AD0{slash}CT32B0M3-Pad42)") (class "Default")
      (node (ref "IC1") (pin "42") (pinfunction "TDI/PIO0.11/AD0/CT32B0M3_42") (pintype "bidirectional"))
    )
    (net (code "91") (name "unconnected-(IC1-TDO{slash}PIO0.13{slash}AD2{slash}CB32B1M0-Pad45)") (class "Default")
      (node (ref "IC1") (pin "45") (pinfunction "TDO/PIO0.13/AD2/CB32B1M0_45") (pintype "bidirectional"))
    )
    (net (code "92") (name "unconnected-(IC1-TMS{slash}PIO0.12{slash}AD1{slash}CT32B1M0-Pad44)") (class "Default")
      (node (ref "IC1") (pin "44") (pinfunction "TMS/PIO0.12/AD1/CT32B1M0_44") (pintype "bidirectional"))
    )
    (net (code "93") (name "unconnected-(J2-PAD1-PadNC1)") (class "Default")
      (node (ref "J2") (pin "NC1") (pinfunction "PAD1_NC1") (pintype "bidirectional"))
    )
    (net (code "94") (name "unconnected-(J2-PAD2-PadNC2)") (class "Default")
      (node (ref "J2") (pin "NC2") (pinfunction "PAD2_NC2") (pintype "bidirectional"))
    )
    (net (code "95") (name "unconnected-(JTAG1-Pad8)") (class "Default")
      (node (ref "JTAG1") (pin "8") (pinfunction "8_8") (pintype "passive"))
    )
    (net (code "96") (name "unconnected-(U1-NC-Pad1)") (class "Default")
      (node (ref "U1") (pin "1") (pinfunction "NC_1") (pintype "bidirectional"))
    )
    (net (code "97") (name "unconnected-(U1-RSV-Pad8)") (class "Default")
      (node (ref "U1") (pin "8") (pinfunction "RSV_8") (pintype "bidirectional"))
    )
    (net (code "98") (name "unconnected-(U1-SHIELD-PadCD1)") (class "Default")
      (node (ref "U1") (pin "CD1") (pinfunction "SHIELD_CD1") (pintype "bidirectional"))
    )
    (net (code "99") (name "unconnected-(U2-CLKIN-Pad1)") (class "Default")
      (node (ref "U2") (pin "1") (pinfunction "CLKIN_1") (pintype "bidirectional"))
    )
    (net (code "100") (name "unconnected-(U2-CLKOUT-Pad22)") (class "Default")
      (node (ref "U2") (pin "22") (pinfunction "CLKOUT_22") (pintype "bidirectional"))
    )
    (net (code "101") (name "unconnected-(U2-FSYNC-Pad11)") (class "Default")
      (node (ref "U2") (pin "11") (pinfunction "FSYNC_11") (pintype "bidirectional"))
    )
    (net (code "102") (name "unconnected-(U5-*INT{slash}SQW-Pad3)") (class "Default")
      (node (ref "U5") (pin "3") (pinfunction "*INT/SQW_3") (pintype "passive"))
    )
    (net (code "103") (name "unconnected-(U5-32KHZ-Pad1)") (class "Default")
      (node (ref "U5") (pin "1") (pinfunction "32KHZ_1") (pintype "passive"))
    )
    (net (code "104") (name "unconnected-(U8-*OUT-Pad4)") (class "Default")
      (node (ref "U8") (pin "4") (pinfunction "*OUT_4") (pintype "output"))
    )
    (net (code "105") (name "unconnected-(U9-AIO0-Pad9)") (class "Default")
      (node (ref "U9") (pin "9") (pinfunction "AIO0_9") (pintype "bidirectional"))
    )
    (net (code "106") (name "unconnected-(U9-AIO1-Pad10)") (class "Default")
      (node (ref "U9") (pin "10") (pinfunction "AIO1_10") (pintype "bidirectional"))
    )
    (net (code "107") (name "unconnected-(U9-CLK-Pad19)") (class "Default")
      (node (ref "U9") (pin "19") (pinfunction "CLK_19") (pintype "bidirectional"))
    )
    (net (code "108") (name "unconnected-(U9-CSB-Pad16)") (class "Default")
      (node (ref "U9") (pin "16") (pinfunction "CSB_16") (pintype "bidirectional"))
    )
    (net (code "109") (name "unconnected-(U9-CTS-Pad3)") (class "Default")
      (node (ref "U9") (pin "3") (pinfunction "CTS_3") (pintype "bidirectional"))
    )
    (net (code "110") (name "unconnected-(U9-GND1-Pad21)") (class "Default")
      (node (ref "U9") (pin "21") (pinfunction "GND1_21") (pintype "bidirectional"))
    )
    (net (code "111") (name "unconnected-(U9-GND2-Pad22)") (class "Default")
      (node (ref "U9") (pin "22") (pinfunction "GND2_22") (pintype "bidirectional"))
    )
    (net (code "112") (name "unconnected-(U9-MISO-Pad18)") (class "Default")
      (node (ref "U9") (pin "18") (pinfunction "MISO_18") (pintype "bidirectional"))
    )
    (net (code "113") (name "unconnected-(U9-MOSI-Pad17)") (class "Default")
      (node (ref "U9") (pin "17") (pinfunction "MOSI_17") (pintype "bidirectional"))
    )
    (net (code "114") (name "unconnected-(U9-NC-Pad14)") (class "Default")
      (node (ref "U9") (pin "14") (pinfunction "NC_14") (pintype "bidirectional"))
    )
    (net (code "115") (name "unconnected-(U9-PCM_CLK-Pad5)") (class "Default")
      (node (ref "U9") (pin "5") (pinfunction "PCM_CLK_5") (pintype "bidirectional"))
    )
    (net (code "116") (name "unconnected-(U9-PCM_IN-Pad7)") (class "Default")
      (node (ref "U9") (pin "7") (pinfunction "PCM_IN_7") (pintype "bidirectional"))
    )
    (net (code "117") (name "unconnected-(U9-PCM_OUT-Pad6)") (class "Default")
      (node (ref "U9") (pin "6") (pinfunction "PCM_OUT_6") (pintype "bidirectional"))
    )
    (net (code "118") (name "unconnected-(U9-PCN_SYNC-Pad8)") (class "Default")
      (node (ref "U9") (pin "8") (pinfunction "PCN_SYNC_8") (pintype "bidirectional"))
    )
    (net (code "119") (name "unconnected-(U9-PIO0-Pad23)") (class "Default")
      (node (ref "U9") (pin "23") (pinfunction "PIO0_23") (pintype "bidirectional"))
    )
    (net (code "120") (name "unconnected-(U9-PIO1-Pad24)") (class "Default")
      (node (ref "U9") (pin "24") (pinfunction "PIO1_24") (pintype "bidirectional"))
    )
    (net (code "121") (name "unconnected-(U9-PIO2-Pad25)") (class "Default")
      (node (ref "U9") (pin "25") (pinfunction "PIO2_25") (pintype "bidirectional"))
    )
    (net (code "122") (name "unconnected-(U9-PIO4-Pad27)") (class "Default")
      (node (ref "U9") (pin "27") (pinfunction "PIO4_27") (pintype "bidirectional"))
    )
    (net (code "123") (name "unconnected-(U9-PIO5-Pad28)") (class "Default")
      (node (ref "U9") (pin "28") (pinfunction "PIO5_28") (pintype "bidirectional"))
    )
    (net (code "124") (name "unconnected-(U9-PIO6-Pad29)") (class "Default")
      (node (ref "U9") (pin "29") (pinfunction "PIO6_29") (pintype "bidirectional"))
    )
    (net (code "125") (name "unconnected-(U9-PIO7-Pad30)") (class "Default")
      (node (ref "U9") (pin "30") (pinfunction "PIO7_30") (pintype "bidirectional"))
    )
    (net (code "126") (name "unconnected-(U9-PIO8-Pad31)") (class "Default")
      (node (ref "U9") (pin "31") (pinfunction "PIO8_31") (pintype "bidirectional"))
    )
    (net (code "127") (name "unconnected-(U9-PIO9-Pad32)") (class "Default")
      (node (ref "U9") (pin "32") (pinfunction "PIO9_32") (pintype "bidirectional"))
    )
    (net (code "128") (name "unconnected-(U9-PIO10-Pad33)") (class "Default")
      (node (ref "U9") (pin "33") (pinfunction "PIO10_33") (pintype "bidirectional"))
    )
    (net (code "129") (name "unconnected-(U9-RTS-Pad4)") (class "Default")
      (node (ref "U9") (pin "4") (pinfunction "RTS_4") (pintype "bidirectional"))
    )
    (net (code "130") (name "unconnected-(U9-VBUSD+-Pad20)") (class "Default")
      (node (ref "U9") (pin "20") (pinfunction "VBUSD+_20") (pintype "bidirectional"))
    )
    (net (code "131") (name "unconnected-(U9-VBUSD--Pad15)") (class "Default")
      (node (ref "U9") (pin "15") (pinfunction "VBUSD-_15") (pintype "bidirectional"))
    )
  )
)
